# arm_power.net
KiCad netlist of a schematic drawn in Altium Designer
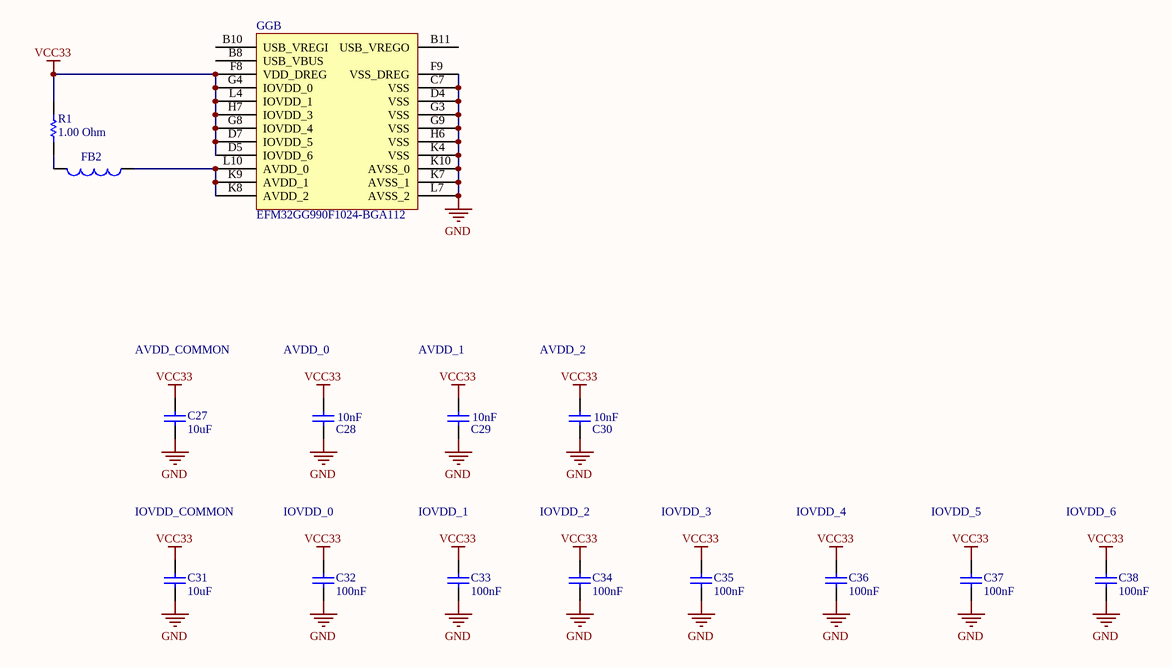
[diagram p0: arm_power.SchDoc]

(export (version "E")
  (design (tool "Eeschema 10.0.6"))
  (components
    (comp (ref "C27")
      (value "10uF")
      (footprint "CAPC0805(2012)145_N")
      (description "CAP 10uF 25V ±10% 0805 (2012 Metric) Thickness 1.45mm SMD")
      (fields (field (name "TOLERANCE") "±10%"))
      (libsource (lib "Altium Content Vault") (part "CMP-1036-04932-1"))
    )
    (comp (ref "C28")
      (value "10nF")
      (footprint "CAPC0805(2012)75_N")
      (description "CAP 10nF 50V ±10% 0805 (2012 Metric) Thickness 0.75mm SMD")
      (fields (field (name "TOLERANCE") "±10%"))
      (libsource (lib "Altium Content Vault") (part "CMP-1036-03842-1"))
    )
    (comp (ref "C29")
      (value "10nF")
      (footprint "CAPC0805(2012)75_N")
      (description "CAP 10nF 50V ±10% 0805 (2012 Metric) Thickness 0.75mm SMD")
      (fields (field (name "TOLERANCE") "±10%"))
      (libsource (lib "Altium Content Vault") (part "CMP-1036-03842-1"))
    )
    (comp (ref "C30")
      (value "10nF")
      (footprint "CAPC0805(2012)75_N")
      (description "CAP 10nF 50V ±10% 0805 (2012 Metric) Thickness 0.75mm SMD")
      (fields (field (name "TOLERANCE") "±10%"))
      (libsource (lib "Altium Content Vault") (part "CMP-1036-03842-1"))
    )
    (comp (ref "C31")
      (value "10uF")
      (footprint "CAPC0805(2012)145_N")
      (description "CAP 10uF 25V ±10% 0805 (2012 Metric) Thickness 1.45mm SMD")
      (fields (field (name "TOLERANCE") "±10%"))
      (libsource (lib "Altium Content Vault") (part "CMP-1036-04932-1"))
    )
    (comp (ref "C32")
      (value "100nF")
      (footprint "CAPC0805(2012)100_M")
      (description "CAP 100nF 50V ±10% 0805 (2012 Metric) Thickness 1mm SMD")
      (fields (field (name "TOLERANCE") "±10%"))
      (libsource (lib "Altium Content Vault") (part "CMP-1036-04420-1"))
    )
    (comp (ref "C33")
      (value "100nF")
      (footprint "CAPC0805(2012)100_M")
      (description "CAP 100nF 50V ±10% 0805 (2012 Metric) Thickness 1mm SMD")
      (fields (field (name "TOLERANCE") "±10%"))
      (libsource (lib "Altium Content Vault") (part "CMP-1036-04420-1"))
    )
    (comp (ref "C34")
      (value "100nF")
      (footprint "CAPC0805(2012)100_M")
      (description "CAP 100nF 50V ±10% 0805 (2012 Metric) Thickness 1mm SMD")
      (fields (field (name "TOLERANCE") "±10%"))
      (libsource (lib "Altium Content Vault") (part "CMP-1036-04420-1"))
    )
    (comp (ref "C35")
      (value "100nF")
      (footprint "CAPC0805(2012)100_M")
      (description "CAP 100nF 50V ±10% 0805 (2012 Metric) Thickness 1mm SMD")
      (fields (field (name "TOLERANCE") "±10%"))
      (libsource (lib "Altium Content Vault") (part "CMP-1036-04420-1"))
    )
    (comp (ref "C36")
      (value "100nF")
      (footprint "CAPC0805(2012)100_M")
      (description "CAP 100nF 50V ±10% 0805 (2012 Metric) Thickness 1mm SMD")
      (fields (field (name "TOLERANCE") "±10%"))
      (libsource (lib "Altium Content Vault") (part "CMP-1036-04420-1"))
    )
    (comp (ref "C37")
      (value "100nF")
      (footprint "CAPC0805(2012)100_M")
      (description "CAP 100nF 50V ±10% 0805 (2012 Metric) Thickness 1mm SMD")
      (fields (field (name "TOLERANCE") "±10%"))
      (libsource (lib "Altium Content Vault") (part "CMP-1036-04420-1"))
    )
    (comp (ref "C38")
      (value "100nF")
      (footprint "CAPC0805(2012)100_M")
      (description "CAP 100nF 50V ±10% 0805 (2012 Metric) Thickness 1mm SMD")
      (fields (field (name "TOLERANCE") "±10%"))
      (libsource (lib "Altium Content Vault") (part "CMP-1036-04420-1"))
    )
    (comp (ref "FB2")
      (value "BLM21B102S or similar")
      (footprint "RESC3216N")
      (description "Inductor")
      (fields (field (name "PUBLISHER") "Altium Limited"))
      (libsource (lib "Miscellaneous Devices") (part "Inductor"))
    )
    (comp (ref "GG")
      (value "EFM32GG990F1024-BGA112")
      (footprint "ENMR-BGA112")
      (fields (field (name "GENERIC PART NUMBER") "EFM32GG990"))
      (libsource (lib "Silicon Labs Energy Micro EFM32") (part "EFM32GG990F1024-BGA112"))
    )
    (comp (ref "R1")
      (value "1.00 Ohm")
      (footprint "RESC0805(2012)_L")
      (description "1R 0.125W 5% 0805 (2012 Metric)  SMD")
      (fields (field (name "POWER") "0.125 W") (field (name "TOLERANCE") "5 %"))
      (libsource (lib "Altium Content Vault") (part "CMP-1013-00002-1"))
    )
  )
  (nets
    (net (code "1") (name "GND") (class "Default")
      (node (ref "C27") (pin "1") (pinfunction "1_1") (pintype "passive"))
      (node (ref "C28") (pin "1") (pinfunction "1_1") (pintype "passive"))
      (node (ref "C29") (pin "1") (pinfunction "1_1") (pintype "passive"))
      (node (ref "C30") (pin "1") (pinfunction "1_1") (pintype "passive"))
      (node (ref "C31") (pin "1") (pinfunction "1_1") (pintype "passive"))
      (node (ref "C32") (pin "1") (pinfunction "1_1") (pintype "passive"))
      (node (ref "C33") (pin "1") (pinfunction "1_1") (pintype "passive"))
      (node (ref "C34") (pin "1") (pinfunction "1_1") (pintype "passive"))
      (node (ref "C35") (pin "1") (pinfunction "1_1") (pintype "passive"))
      (node (ref "C36") (pin "1") (pinfunction "1_1") (pintype "passive"))
      (node (ref "C37") (pin "1") (pinfunction "1_1") (pintype "passive"))
      (node (ref "C38") (pin "1") (pinfunction "1_1") (pintype "passive"))
      (node (ref "GG") (pin "C7") (pinfunction "VSS_C7") (pintype "power_in"))
      (node (ref "GG") (pin "D4") (pinfunction "VSS_D4") (pintype "power_in"))
      (node (ref "GG") (pin "F9") (pinfunction "VSS_DREG_F9") (pintype "power_in"))
      (node (ref "GG") (pin "G3") (pinfunction "VSS_G3") (pintype "power_in"))
      (node (ref "GG") (pin "G9") (pinfunction "VSS_G9") (pintype "power_in"))
      (node (ref "GG") (pin "H6") (pinfunction "VSS_H6") (pintype "power_in"))
      (node (ref "GG") (pin "K10") (pinfunction "AVSS_0_K10") (pintype "power_in"))
      (node (ref "GG") (pin "K4") (pinfunction "VSS_K4") (pintype "power_in"))
      (node (ref "GG") (pin "K7") (pinfunction "AVSS_1_K7") (pintype "power_in"))
      (node (ref "GG") (pin "L7") (pinfunction "AVSS_2_L7") (pintype "power_in"))
    )
    (net (code "2") (name "Net-(FB2-Pad2)") (class "Default")
      (node (ref "FB2") (pin "2") (pinfunction "2_2") (pintype "passive"))
      (node (ref "R1") (pin "1") (pinfunction "1_1") (pintype "passive"))
    )
    (net (code "3") (name "Net-(GGB-AVDD_0)") (class "Default")
      (node (ref "FB2") (pin "1") (pinfunction "1_1") (pintype "passive"))
      (node (ref "GG") (pin "K8") (pinfunction "AVDD_2_K8") (pintype "power_in"))
      (node (ref "GG") (pin "K9") (pinfunction "AVDD_1_K9") (pintype "power_in"))
      (node (ref "GG") (pin "L10") (pinfunction "AVDD_0_L10") (pintype "power_in"))
    )
    (net (code "4") (name "VCC33") (class "Default")
      (node (ref "C27") (pin "2") (pinfunction "2_2") (pintype "passive"))
      (node (ref "C28") (pin "2") (pinfunction "2_2") (pintype "passive"))
      (node (ref "C29") (pin "2") (pinfunction "2_2") (pintype "passive"))
      (node (ref "C30") (pin "2") (pinfunction "2_2") (pintype "passive"))
      (node (ref "C31") (pin "2") (pinfunction "2_2") (pintype "passive"))
      (node (ref "C32") (pin "2") (pinfunction "2_2") (pintype "passive"))
      (node (ref "C33") (pin "2") (pinfunction "2_2") (pintype "passive"))
      (node (ref "C34") (pin "2") (pinfunction "2_2") (pintype "passive"))
      (node (ref "C35") (pin "2") (pinfunction "2_2") (pintype "passive"))
      (node (ref "C36") (pin "2") (pinfunction "2_2") (pintype "passive"))
      (node (ref "C37") (pin "2") (pinfunction "2_2") (pintype "passive"))
      (node (ref "C38") (pin "2") (pinfunction "2_2") (pintype "passive"))
      (node (ref "GG") (pin "D5") (pinfunction "IOVDD_6_D5") (pintype "power_in"))
      (node (ref "GG") (pin "D7") (pinfunction "IOVDD_5_D7") (pintype "power_in"))
      (node (ref "GG") (pin "F8") (pinfunction "VDD_DREG_F8") (pintype "power_in"))
      (node (ref "GG") (pin "G4") (pinfunction "IOVDD_0_G4") (pintype "power_in"))
      (node (ref "GG") (pin "G8") (pinfunction "IOVDD_4_G8") (pintype "power_in"))
      (node (ref "GG") (pin "H7") (pinfunction "IOVDD_3_H7") (pintype "power_in"))
      (node (ref "GG") (pin "L4") (pinfunction "IOVDD_1_L4") (pintype "power_in"))
      (node (ref "R1") (pin "2") (pinfunction "2_2") (pintype "passive"))
    )
    (net (code "5") (name "unconnected-(GGB-USB_VBUS-PadB8)") (class "Default")
      (node (ref "GG") (pin "B8") (pinfunction "USB_VBUS_B8") (pintype "power_in"))
    )
    (net (code "6") (name "unconnected-(GGB-USB_VREGI-PadB10)") (class "Default")
      (node (ref "GG") (pin "B10") (pinfunction "USB_VREGI_B10") (pintype "power_in"))
    )
    (net (code "7") (name "unconnected-(GGB-USB_VREGO-PadB11)") (class "Default")
      (node (ref "GG") (pin "B11") (pinfunction "USB_VREGO_B11") (pintype "passive"))
    )
  )
)
